# cc2652p_ch340k.net
KiCad netlist of a schematic drawn in EAGLE
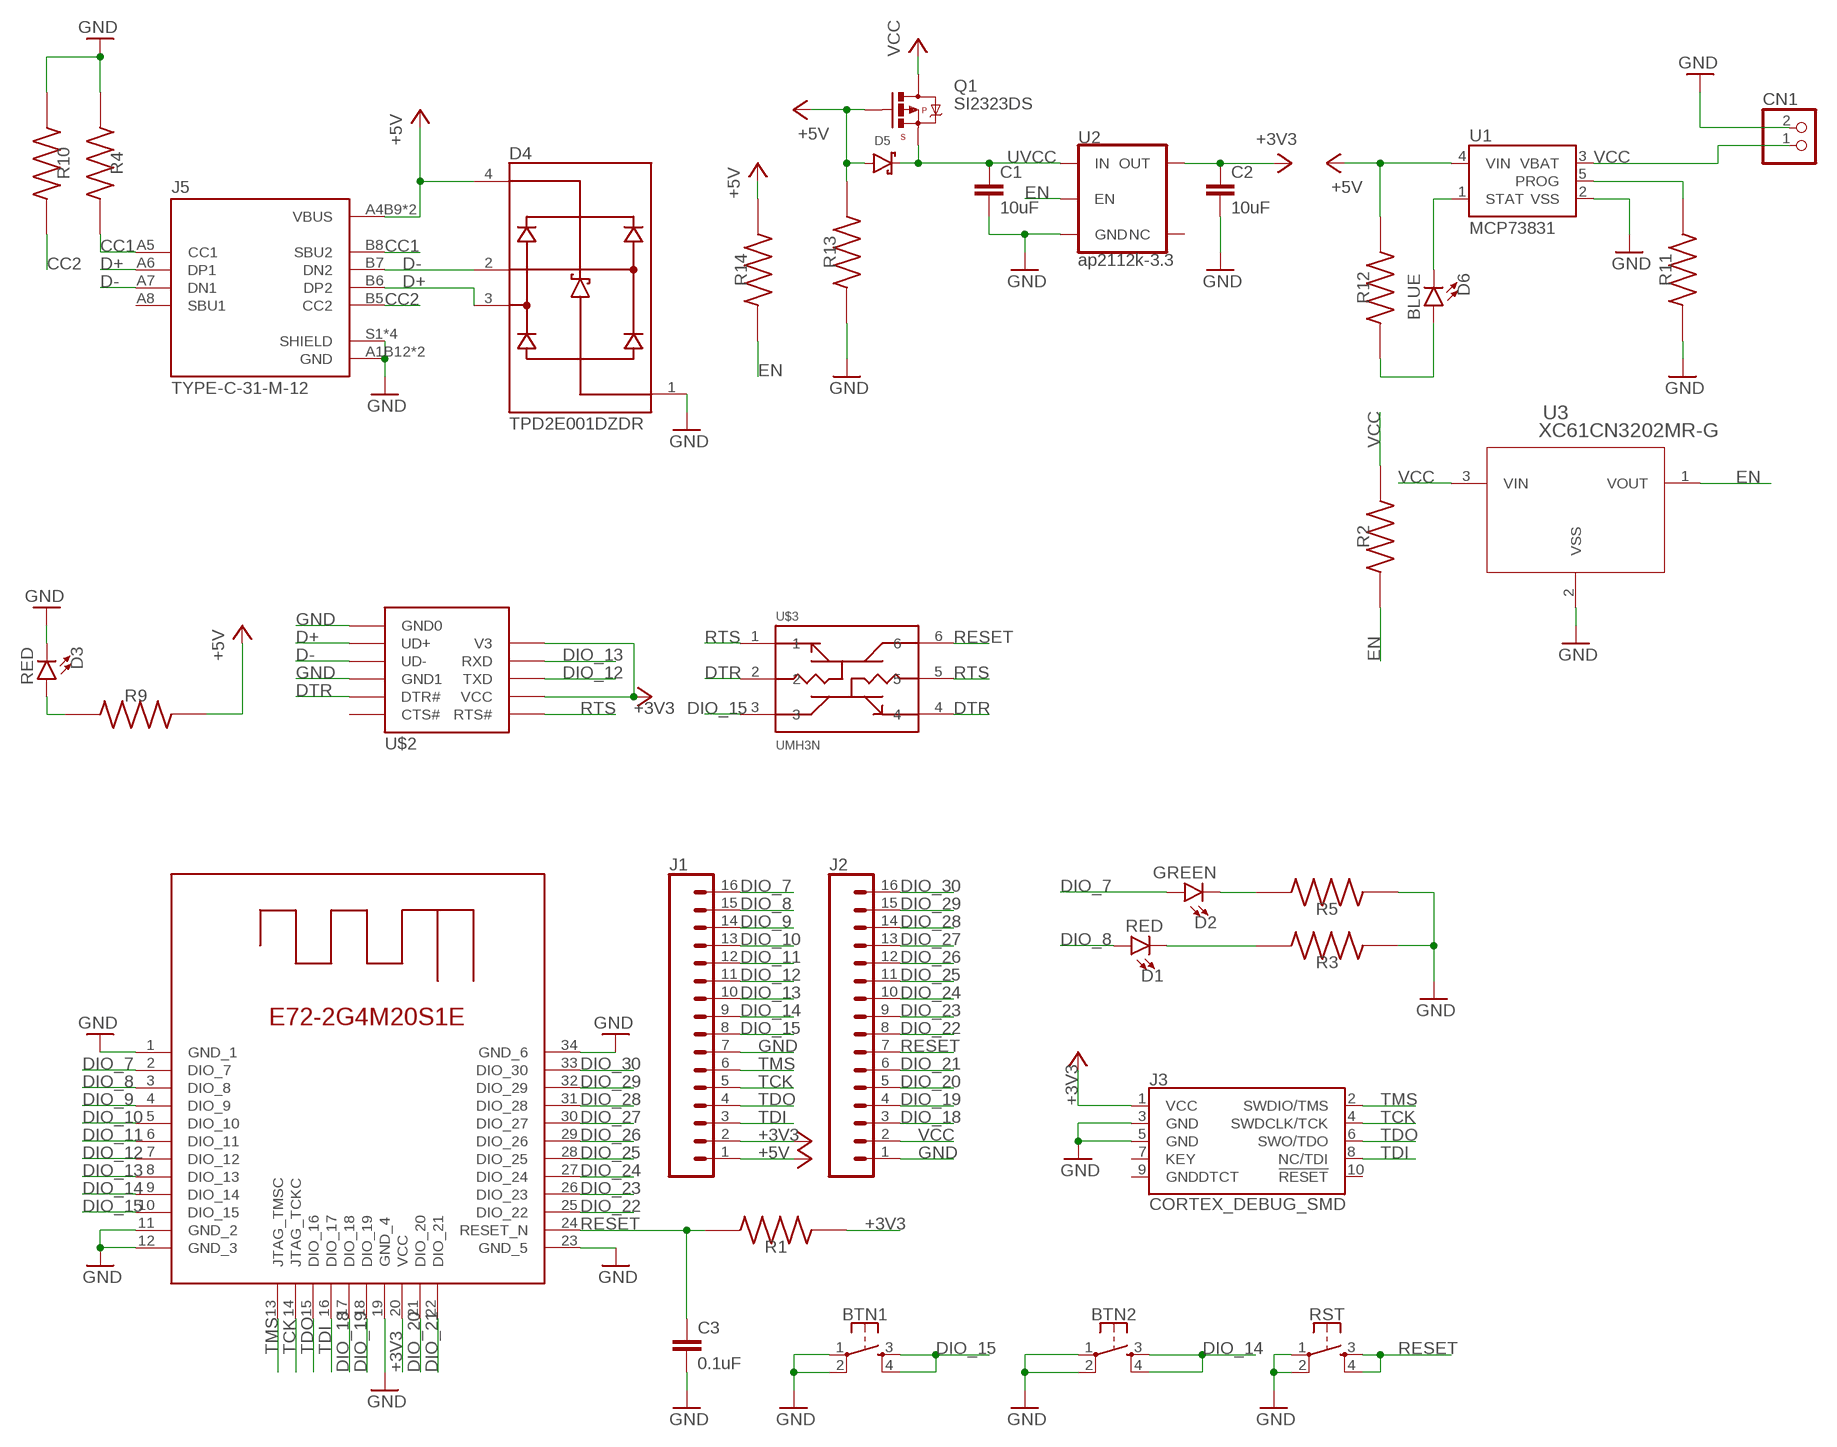
[diagram p0: schematic, sheet 1]

(export (version "E")
  (design (tool "Eeschema 10.0.6"))
  (components
    (comp (ref "BTN1")
      (value "MOMENTARY-SWITCH-SPST-2-SMD-4.6X2.8MM")
      (footprint "eagle-import:TACTILE_SWITCH_SMD_4.6X2.8MM")
      (libsource (lib "eagle-import") (part "MOMENTARY-SWITCH-SPST-2-SMD-4.6X2.8MM"))
    )
    (comp (ref "BTN2")
      (value "MOMENTARY-SWITCH-SPST-2-SMD-4.6X2.8MM")
      (footprint "eagle-import:TACTILE_SWITCH_SMD_4.6X2.8MM")
      (libsource (lib "eagle-import") (part "MOMENTARY-SWITCH-SPST-2-SMD-4.6X2.8MM"))
    )
    (comp (ref "C1")
      (value "10uF")
      (footprint "eagle-import:0603")
      (libsource (lib "eagle-import") (part "10UF-0603-6.3V-20%"))
    )
    (comp (ref "C2")
      (value "10uF")
      (footprint "eagle-import:0603")
      (libsource (lib "eagle-import") (part "10UF-0603-6.3V-20%"))
    )
    (comp (ref "C3")
      (value "0.1uF")
      (footprint "eagle-import:0603")
      (libsource (lib "eagle-import") (part "0.1UF-0603-25V-(+80/-20%)"))
    )
    (comp (ref "CN1")
      (value "JST_2PIN-SMT-RA")
      (footprint "eagle-import:JST-PH-2-SMT-RA")
      (libsource (lib "eagle-import") (part "JST_2PIN-SMT-RA"))
    )
    (comp (ref "D1")
      (value "RED")
      (footprint "eagle-import:LED-0603")
      (libsource (lib "eagle-import") (part "LED-RED0603"))
    )
    (comp (ref "D2")
      (value "GREEN")
      (footprint "eagle-import:LED-0603")
      (libsource (lib "eagle-import") (part "LED-GREEN0603"))
    )
    (comp (ref "D3")
      (value "RED")
      (footprint "eagle-import:LED-0603")
      (libsource (lib "eagle-import") (part "LED-RED0603"))
    )
    (comp (ref "D4")
      (value "TPD2E001DZDR")
      (footprint "eagle-import:SOT192P237X122-4N")
      (fields (field (name "MF") "Texas Instruments"))
      (libsource (lib "eagle-import") (part "TPD2E001DZDR"))
    )
    (comp (ref "D5")
      (value "DIODE-SCHOTTKY")
      (footprint "eagle-import:SOD-323")
      (libsource (lib "eagle-import") (part "DIODE-SCHOTTKY"))
    )
    (comp (ref "D6")
      (value "BLUE")
      (footprint "eagle-import:LED-0603")
      (libsource (lib "eagle-import") (part "LED-BLUE0603"))
    )
    (comp (ref "J1")
      (value "CONN_161X16_NO_SILK")
      (footprint "eagle-import:1X16_NO_SILK")
      (libsource (lib "eagle-import") (part "CONN_161X16_NO_SILK"))
    )
    (comp (ref "J2")
      (value "CONN_161X16_NO_SILK")
      (footprint "eagle-import:1X16_NO_SILK")
      (libsource (lib "eagle-import") (part "CONN_161X16_NO_SILK"))
    )
    (comp (ref "J3")
      (value "CORTEX_DEBUG_SMD")
      (footprint "eagle-import:SAMTECH_FTSH-105-01")
      (libsource (lib "eagle-import") (part "CORTEX_DEBUG_SMD"))
    )
    (comp (ref "J5")
      (value "TYPE-C-31-M-12")
      (footprint "eagle-import:HRO_TYPE-C-31-M-12")
      (fields (field (name "MF") "HRO Electronics Co., Ltd."))
      (libsource (lib "eagle-import") (part "TYPE-C-31-M-12"))
    )
    (comp (ref "Q1")
      (value "SI2323DS")
      (footprint "eagle-import:SOT23")
      (libsource (lib "eagle-import") (part "MOSFET-PCHANNEL"))
    )
    (comp (ref "R1")
      (value "100k")
      (footprint "eagle-import:RESC1005X40N")
      (fields (field (name "MF") "Yageo") (field (name "MP") "RC0402FR-073M6L"))
      (libsource (lib "eagle-import") (part "RC0402FR-073M6L"))
    )
    (comp (ref "R2")
      (value "10k")
      (footprint "eagle-import:RESC1005X40N")
      (fields (field (name "MF") "Yageo") (field (name "MP") "RC0402FR-073M6L"))
      (libsource (lib "eagle-import") (part "RC0402FR-073M6L"))
    )
    (comp (ref "R3")
      (value "2.2k")
      (footprint "eagle-import:RESC1005X40N")
      (fields (field (name "MF") "Yageo") (field (name "MP") "RC0402FR-073M6L"))
      (libsource (lib "eagle-import") (part "RC0402FR-073M6L"))
    )
    (comp (ref "R4")
      (value "5.1k")
      (footprint "eagle-import:RESC1005X40N")
      (fields (field (name "MF") "Yageo") (field (name "MP") "RC0402FR-073M6L"))
      (libsource (lib "eagle-import") (part "RC0402FR-073M6L"))
    )
    (comp (ref "R5")
      (value "2.2k")
      (footprint "eagle-import:RESC1005X40N")
      (fields (field (name "MF") "Yageo") (field (name "MP") "RC0402FR-073M6L"))
      (libsource (lib "eagle-import") (part "RC0402FR-073M6L"))
    )
    (comp (ref "R9")
      (value "2.2k")
      (footprint "eagle-import:RESC1005X40N")
      (fields (field (name "MF") "Yageo") (field (name "MP") "RC0402FR-073M6L"))
      (libsource (lib "eagle-import") (part "RC0402FR-073M6L"))
    )
    (comp (ref "R10")
      (value "5.1k")
      (footprint "eagle-import:RESC1005X40N")
      (fields (field (name "MF") "Yageo") (field (name "MP") "RC0402FR-073M6L"))
      (libsource (lib "eagle-import") (part "RC0402FR-073M6L"))
    )
    (comp (ref "R11")
      (value "2k")
      (footprint "eagle-import:RESC1005X40N")
      (fields (field (name "MF") "Yageo") (field (name "MP") "RC0402FR-073M6L"))
      (libsource (lib "eagle-import") (part "RC0402FR-073M6L"))
    )
    (comp (ref "R12")
      (value "2.2k")
      (footprint "eagle-import:RESC1005X40N")
      (fields (field (name "MF") "Yageo") (field (name "MP") "RC0402FR-073M6L"))
      (libsource (lib "eagle-import") (part "RC0402FR-073M6L"))
    )
    (comp (ref "R13")
      (value "10k")
      (footprint "eagle-import:RESC1005X40N")
      (fields (field (name "MF") "Yageo") (field (name "MP") "RC0402FR-073M6L"))
      (libsource (lib "eagle-import") (part "RC0402FR-073M6L"))
    )
    (comp (ref "R14")
      (value "10k")
      (footprint "eagle-import:RESC1005X40N")
      (fields (field (name "MF") "Yageo") (field (name "MP") "RC0402FR-073M6L"))
      (libsource (lib "eagle-import") (part "RC0402FR-073M6L"))
    )
    (comp (ref "RST")
      (value "MOMENTARY-SWITCH-SPST-2-SMD-4.6X2.8MM")
      (footprint "eagle-import:TACTILE_SWITCH_SMD_4.6X2.8MM")
      (libsource (lib "eagle-import") (part "MOMENTARY-SWITCH-SPST-2-SMD-4.6X2.8MM"))
    )
    (comp (ref "U$1")
      (value "E72-2G4M20S1E")
      (footprint "eagle-import:E72-2G4M20S1E")
      (libsource (lib "eagle-import") (part "E72-2G4M20S1E"))
    )
    (comp (ref "U$2")
      (value "CH340K")
      (footprint "eagle-import:ESSOP10")
      (libsource (lib "eagle-import") (part "CH340K"))
    )
    (comp (ref "U$3")
      (value "UMH3N")
      (footprint "eagle-import:SOP65P210X100-6N")
      (fields (field (name "MF") "Rohm"))
      (libsource (lib "eagle-import") (part "UMH3N"))
    )
    (comp (ref "U1")
      (value "MCP73831")
      (footprint "eagle-import:SOT23-5")
      (libsource (lib "eagle-import") (part "MCP73831"))
    )
    (comp (ref "U2")
      (value "ap2112k-3.3")
      (footprint "eagle-import:SOT23-5")
      (libsource (lib "eagle-import") (part "V_REG_AP2112K-3.3V"))
    )
    (comp (ref "U3")
      (value "XC61CN3202MR-G")
      (footprint "eagle-import:XC61C_SOT-23_TOR")
      (libsource (lib "eagle-import") (part "XC61CN3202MR-G"))
    )
  )
  (nets
    (net (code "1") (name "+3V3") (class "Default")
      (node (ref "C2") (pin "1") (pinfunction "1_1") (pintype "passive"))
      (node (ref "J1") (pin "2") (pinfunction "2_2") (pintype "passive"))
      (node (ref "J3") (pin "1") (pinfunction "VCC_1") (pintype "bidirectional"))
      (node (ref "R1") (pin "1") (pinfunction "1_1") (pintype "passive"))
      (node (ref "U$1") (pin "20") (pinfunction "VCC_20") (pintype "bidirectional"))
      (node (ref "U$2") (pin "P$6") (pinfunction "VCC_P$6") (pintype "bidirectional"))
      (node (ref "U$2") (pin "P$9") (pinfunction "V3_P$9") (pintype "bidirectional"))
      (node (ref "U2") (pin "5") (pinfunction "OUT_5") (pintype "passive"))
    )
    (net (code "2") (name "+5V") (class "Default")
      (node (ref "D4") (pin "4") (pinfunction "VCC_4") (pintype "power_in"))
      (node (ref "D5") (pin "A") (pinfunction "A_A") (pintype "passive"))
      (node (ref "J1") (pin "1") (pinfunction "1_1") (pintype "passive"))
      (node (ref "J5") (pin "A4B9") (pinfunction "VBUS_A4B9") (pintype "power_in"))
      (node (ref "J5") (pin "B4A9") (pinfunction "VBUS_B4A9") (pintype "power_in"))
      (node (ref "Q1") (pin "1") (pinfunction "G_1") (pintype "passive"))
      (node (ref "R12") (pin "2") (pinfunction "2_2") (pintype "passive"))
      (node (ref "R13") (pin "2") (pinfunction "2_2") (pintype "passive"))
      (node (ref "R14") (pin "2") (pinfunction "2_2") (pintype "passive"))
      (node (ref "R9") (pin "1") (pinfunction "1_1") (pintype "passive"))
      (node (ref "U1") (pin "4") (pinfunction "VIN_4") (pintype "power_in"))
    )
    (net (code "3") (name "/CC1") (class "Default")
      (node (ref "J5") (pin "A5") (pinfunction "CC1_A5") (pintype "bidirectional"))
      (node (ref "J5") (pin "B8") (pinfunction "SBU2_B8") (pintype "bidirectional"))
      (node (ref "R4") (pin "2") (pinfunction "2_2") (pintype "passive"))
    )
    (net (code "4") (name "/CC2") (class "Default")
      (node (ref "J5") (pin "B5") (pinfunction "CC2_B5") (pintype "bidirectional"))
      (node (ref "R10") (pin "2") (pinfunction "2_2") (pintype "passive"))
    )
    (net (code "5") (name "/D+") (class "Default")
      (node (ref "D4") (pin "3") (pinfunction "IO2_3") (pintype "bidirectional"))
      (node (ref "J5") (pin "A6") (pinfunction "DP1_A6") (pintype "bidirectional"))
      (node (ref "J5") (pin "B6") (pinfunction "DP2_B6") (pintype "bidirectional"))
      (node (ref "U$2") (pin "P$0") (pinfunction "UD+_P$0") (pintype "bidirectional"))
    )
    (net (code "6") (name "/D-") (class "Default")
      (node (ref "D4") (pin "2") (pinfunction "IO1_2") (pintype "bidirectional"))
      (node (ref "J5") (pin "A7") (pinfunction "DN1_A7") (pintype "bidirectional"))
      (node (ref "J5") (pin "B7") (pinfunction "DN2_B7") (pintype "bidirectional"))
      (node (ref "U$2") (pin "P$1") (pinfunction "UD-_P$1") (pintype "bidirectional"))
    )
    (net (code "7") (name "/DIO_7") (class "Default")
      (node (ref "D2") (pin "A") (pinfunction "A_A") (pintype "passive"))
      (node (ref "J1") (pin "16") (pinfunction "16_16") (pintype "passive"))
      (node (ref "U$1") (pin "2") (pinfunction "DIO_7_2") (pintype "bidirectional"))
    )
    (net (code "8") (name "/DIO_8") (class "Default")
      (node (ref "D1") (pin "A") (pinfunction "A_A") (pintype "passive"))
      (node (ref "J1") (pin "15") (pinfunction "15_15") (pintype "passive"))
      (node (ref "U$1") (pin "3") (pinfunction "DIO_8_3") (pintype "bidirectional"))
    )
    (net (code "9") (name "/DIO_9") (class "Default")
      (node (ref "J1") (pin "14") (pinfunction "14_14") (pintype "passive"))
      (node (ref "U$1") (pin "4") (pinfunction "DIO_9_4") (pintype "bidirectional"))
    )
    (net (code "10") (name "/DIO_10") (class "Default")
      (node (ref "J1") (pin "13") (pinfunction "13_13") (pintype "passive"))
      (node (ref "U$1") (pin "5") (pinfunction "DIO_10_5") (pintype "bidirectional"))
    )
    (net (code "11") (name "/DIO_11") (class "Default")
      (node (ref "J1") (pin "12") (pinfunction "12_12") (pintype "passive"))
      (node (ref "U$1") (pin "6") (pinfunction "DIO_11_6") (pintype "bidirectional"))
    )
    (net (code "12") (name "/DIO_12") (class "Default")
      (node (ref "J1") (pin "11") (pinfunction "11_11") (pintype "passive"))
      (node (ref "U$1") (pin "7") (pinfunction "DIO_12_7") (pintype "bidirectional"))
      (node (ref "U$2") (pin "P$7") (pinfunction "TXD_P$7") (pintype "bidirectional"))
    )
    (net (code "13") (name "/DIO_13") (class "Default")
      (node (ref "J1") (pin "10") (pinfunction "10_10") (pintype "passive"))
      (node (ref "U$1") (pin "8") (pinfunction "DIO_13_8") (pintype "bidirectional"))
      (node (ref "U$2") (pin "P$8") (pinfunction "RXD_P$8") (pintype "bidirectional"))
    )
    (net (code "14") (name "/DIO_14") (class "Default")
      (node (ref "BTN2") (pin "3") (pinfunction "3_3") (pintype "passive"))
      (node (ref "BTN2") (pin "4") (pinfunction "4_4") (pintype "passive"))
      (node (ref "J1") (pin "9") (pinfunction "9_9") (pintype "passive"))
      (node (ref "U$1") (pin "9") (pinfunction "DIO_14_9") (pintype "bidirectional"))
    )
    (net (code "15") (name "/DIO_15") (class "Default")
      (node (ref "BTN1") (pin "3") (pinfunction "3_3") (pintype "passive"))
      (node (ref "BTN1") (pin "4") (pinfunction "4_4") (pintype "passive"))
      (node (ref "J1") (pin "8") (pinfunction "8_8") (pintype "passive"))
      (node (ref "U$1") (pin "10") (pinfunction "DIO_15_10") (pintype "bidirectional"))
      (node (ref "U$3") (pin "3") (pinfunction "3_3") (pintype "bidirectional"))
    )
    (net (code "16") (name "/DIO_18") (class "Default")
      (node (ref "J2") (pin "3") (pinfunction "3_3") (pintype "passive"))
      (node (ref "U$1") (pin "17") (pinfunction "DIO_18_17") (pintype "bidirectional"))
    )
    (net (code "17") (name "/DIO_19") (class "Default")
      (node (ref "J2") (pin "4") (pinfunction "4_4") (pintype "passive"))
      (node (ref "U$1") (pin "18") (pinfunction "DIO_19_18") (pintype "bidirectional"))
    )
    (net (code "18") (name "/DIO_20") (class "Default")
      (node (ref "J2") (pin "5") (pinfunction "5_5") (pintype "passive"))
      (node (ref "U$1") (pin "21") (pinfunction "DIO_20_21") (pintype "bidirectional"))
    )
    (net (code "19") (name "/DIO_21") (class "Default")
      (node (ref "J2") (pin "6") (pinfunction "6_6") (pintype "passive"))
      (node (ref "U$1") (pin "22") (pinfunction "DIO_21_22") (pintype "bidirectional"))
    )
    (net (code "20") (name "/DIO_22") (class "Default")
      (node (ref "J2") (pin "8") (pinfunction "8_8") (pintype "passive"))
      (node (ref "U$1") (pin "25") (pinfunction "DIO_22_25") (pintype "bidirectional"))
    )
    (net (code "21") (name "/DIO_23") (class "Default")
      (node (ref "J2") (pin "9") (pinfunction "9_9") (pintype "passive"))
      (node (ref "U$1") (pin "26") (pinfunction "DIO_23_26") (pintype "bidirectional"))
    )
    (net (code "22") (name "/DIO_24") (class "Default")
      (node (ref "J2") (pin "10") (pinfunction "10_10") (pintype "passive"))
      (node (ref "U$1") (pin "27") (pinfunction "DIO_24_27") (pintype "bidirectional"))
    )
    (net (code "23") (name "/DIO_25") (class "Default")
      (node (ref "J2") (pin "11") (pinfunction "11_11") (pintype "passive"))
      (node (ref "U$1") (pin "28") (pinfunction "DIO_25_28") (pintype "bidirectional"))
    )
    (net (code "24") (name "/DIO_26") (class "Default")
      (node (ref "J2") (pin "12") (pinfunction "12_12") (pintype "passive"))
      (node (ref "U$1") (pin "29") (pinfunction "DIO_26_29") (pintype "bidirectional"))
    )
    (net (code "25") (name "/DIO_27") (class "Default")
      (node (ref "J2") (pin "13") (pinfunction "13_13") (pintype "passive"))
      (node (ref "U$1") (pin "30") (pinfunction "DIO_27_30") (pintype "bidirectional"))
    )
    (net (code "26") (name "/DIO_28") (class "Default")
      (node (ref "J2") (pin "14") (pinfunction "14_14") (pintype "passive"))
      (node (ref "U$1") (pin "31") (pinfunction "DIO_28_31") (pintype "bidirectional"))
    )
    (net (code "27") (name "/DIO_29") (class "Default")
      (node (ref "J2") (pin "15") (pinfunction "15_15") (pintype "passive"))
      (node (ref "U$1") (pin "32") (pinfunction "DIO_29_32") (pintype "bidirectional"))
    )
    (net (code "28") (name "/DIO_30") (class "Default")
      (node (ref "J2") (pin "16") (pinfunction "16_16") (pintype "passive"))
      (node (ref "U$1") (pin "33") (pinfunction "DIO_30_33") (pintype "bidirectional"))
    )
    (net (code "29") (name "/DTR") (class "Default")
      (node (ref "U$2") (pin "P$3") (pinfunction "DTR#_P$3") (pintype "bidirectional"))
      (node (ref "U$3") (pin "2") (pinfunction "2_2") (pintype "bidirectional"))
      (node (ref "U$3") (pin "4") (pinfunction "4_4") (pintype "bidirectional"))
    )
    (net (code "30") (name "/EN") (class "Default")
      (node (ref "R14") (pin "1") (pinfunction "1_1") (pintype "passive"))
      (node (ref "R2") (pin "1") (pinfunction "1_1") (pintype "passive"))
      (node (ref "U2") (pin "3") (pinfunction "EN_3") (pintype "input"))
      (node (ref "U3") (pin "1") (pinfunction "VOUT_1") (pintype "output"))
    )
    (net (code "31") (name "/RESET") (class "Default")
      (node (ref "C3") (pin "1") (pinfunction "1_1") (pintype "passive"))
      (node (ref "J2") (pin "7") (pinfunction "7_7") (pintype "passive"))
      (node (ref "R1") (pin "2") (pinfunction "2_2") (pintype "passive"))
      (node (ref "RST") (pin "3") (pinfunction "3_3") (pintype "passive"))
      (node (ref "RST") (pin "4") (pinfunction "4_4") (pintype "passive"))
      (node (ref "U$1") (pin "24") (pinfunction "RESET_N_24") (pintype "bidirectional"))
      (node (ref "U$3") (pin "6") (pinfunction "6_6") (pintype "bidirectional"))
    )
    (net (code "32") (name "/RTS") (class "Default")
      (node (ref "U$2") (pin "P$5") (pinfunction "RTS#_P$5") (pintype "bidirectional"))
      (node (ref "U$3") (pin "1") (pinfunction "1_1") (pintype "bidirectional"))
      (node (ref "U$3") (pin "5") (pinfunction "5_5") (pintype "bidirectional"))
    )
    (net (code "33") (name "/TCK") (class "Default")
      (node (ref "J1") (pin "5") (pinfunction "5_5") (pintype "passive"))
      (node (ref "J3") (pin "4") (pinfunction "SWDCLK/TCK_4") (pintype "bidirectional"))
      (node (ref "U$1") (pin "14") (pinfunction "JTAG_TCKC_14") (pintype "bidirectional"))
    )
    (net (code "34") (name "/TDI") (class "Default")
      (node (ref "J1") (pin "3") (pinfunction "3_3") (pintype "passive"))
      (node (ref "J3") (pin "8") (pinfunction "NC/TDI_8") (pintype "bidirectional"))
      (node (ref "U$1") (pin "16") (pinfunction "DIO_17_16") (pintype "bidirectional"))
    )
    (net (code "35") (name "/TDO") (class "Default")
      (node (ref "J1") (pin "4") (pinfunction "4_4") (pintype "passive"))
      (node (ref "J3") (pin "6") (pinfunction "SWO/TDO_6") (pintype "bidirectional"))
      (node (ref "U$1") (pin "15") (pinfunction "DIO_16_15") (pintype "bidirectional"))
    )
    (net (code "36") (name "/TMS") (class "Default")
      (node (ref "J1") (pin "6") (pinfunction "6_6") (pintype "passive"))
      (node (ref "J3") (pin "2") (pinfunction "SWDIO/TMS_2") (pintype "bidirectional"))
      (node (ref "U$1") (pin "13") (pinfunction "JTAG_TMSC_13") (pintype "bidirectional"))
    )
    (net (code "37") (name "/UVCC") (class "Default")
      (node (ref "C1") (pin "1") (pinfunction "1_1") (pintype "passive"))
      (node (ref "D5") (pin "C") (pinfunction "C_C") (pintype "passive"))
      (node (ref "Q1") (pin "2") (pinfunction "S_2") (pintype "passive"))
      (node (ref "U2") (pin "1") (pinfunction "IN_1") (pintype "input"))
    )
    (net (code "38") (name "GND") (class "Default")
      (node (ref "BTN1") (pin "1") (pinfunction "1_1") (pintype "passive"))
      (node (ref "BTN1") (pin "2") (pinfunction "2_2") (pintype "passive"))
      (node (ref "BTN2") (pin "1") (pinfunction "1_1") (pintype "passive"))
      (node (ref "BTN2") (pin "2") (pinfunction "2_2") (pintype "passive"))
      (node (ref "C1") (pin "2") (pinfunction "2_2") (pintype "passive"))
      (node (ref "C2") (pin "2") (pinfunction "2_2") (pintype "passive"))
      (node (ref "C3") (pin "2") (pinfunction "2_2") (pintype "passive"))
      (node (ref "CN1") (pin "2") (pinfunction "1_2") (pintype "passive"))
      (node (ref "D3") (pin "C") (pinfunction "C_C") (pintype "passive"))
      (node (ref "D4") (pin "1") (pinfunction "GND_1") (pintype "power_in"))
      (node (ref "J1") (pin "7") (pinfunction "7_7") (pintype "passive"))
      (node (ref "J2") (pin "1") (pinfunction "1_1") (pintype "passive"))
      (node (ref "J3") (pin "3") (pinfunction "GND_3") (pintype "bidirectional"))
      (node (ref "J3") (pin "5") (pinfunction "GND_5") (pintype "bidirectional"))
      (node (ref "J5") (pin "A1B12") (pinfunction "GND_A1B12") (pintype "power_in"))
      (node (ref "J5") (pin "B1A12") (pinfunction "GND_B1A12") (pintype "power_in"))
      (node (ref "J5") (pin "S1") (pinfunction "SHIELD_S1") (pintype "passive"))
      (node (ref "J5") (pin "S2") (pinfunction "SHIELD_S2") (pintype "passive"))
      (node (ref "J5") (pin "S3") (pinfunction "SHIELD_S3") (pintype "passive"))
      (node (ref "J5") (pin "S4") (pinfunction "SHIELD_S4") (pintype "passive"))
      (node (ref "R10") (pin "1") (pinfunction "1_1") (pintype "passive"))
      (node (ref "R11") (pin "1") (pinfunction "1_1") (pintype "passive"))
      (node (ref "R13") (pin "1") (pinfunction "1_1") (pintype "passive"))
      (node (ref "R3") (pin "1") (pinfunction "1_1") (pintype "passive"))
      (node (ref "R4") (pin "1") (pinfunction "1_1") (pintype "passive"))
      (node (ref "R5") (pin "1") (pinfunction "1_1") (pintype "passive"))
      (node (ref "RST") (pin "1") (pinfunction "1_1") (pintype "passive"))
      (node (ref "RST") (pin "2") (pinfunction "2_2") (pintype "passive"))
      (node (ref "U$1") (pin "1") (pinfunction "GND_1_1") (pintype "bidirectional"))
      (node (ref "U$1") (pin "11") (pinfunction "GND_2_11") (pintype "bidirectional"))
      (node (ref "U$1") (pin "12") (pinfunction "GND_3_12") (pintype "bidirectional"))
      (node (ref "U$1") (pin "19") (pinfunction "GND_4_19") (pintype "bidirectional"))
      (node (ref "U$1") (pin "23") (pinfunction "GND_5_23") (pintype "bidirectional"))
      (node (ref "U$1") (pin "34") (pinfunction "GND_6_34") (pintype "bidirectional"))
      (node (ref "U$2") (pin "P$10") (pinfunction "GND0_P$10") (pintype "bidirectional"))
      (node (ref "U$2") (pin "P$2") (pinfunction "GND1_P$2") (pintype "bidirectional"))
      (node (ref "U1") (pin "2") (pinfunction "VSS_2") (pintype "power_in"))
      (node (ref "U2") (pin "2") (pinfunction "GND_2") (pintype "input"))
      (node (ref "U3") (pin "2") (pinfunction "VSS_2") (pintype "passive"))
    )
    (net (code "39") (name "Net-(D1-PadC)") (class "Default")
      (node (ref "D1") (pin "C") (pinfunction "C_C") (pintype "passive"))
      (node (ref "R3") (pin "2") (pinfunction "2_2") (pintype "passive"))
    )
    (net (code "40") (name "Net-(D2-PadC)") (class "Default")
      (node (ref "D2") (pin "C") (pinfunction "C_C") (pintype "passive"))
      (node (ref "R5") (pin "2") (pinfunction "2_2") (pintype "passive"))
    )
    (net (code "41") (name "Net-(D3-PadA)") (class "Default")
      (node (ref "D3") (pin "A") (pinfunction "A_A") (pintype "passive"))
      (node (ref "R9") (pin "2") (pinfunction "2_2") (pintype "passive"))
    )
    (net (code "42") (name "Net-(D6-PadA)") (class "Default")
      (node (ref "D6") (pin "A") (pinfunction "A_A") (pintype "passive"))
      (node (ref "R12") (pin "1") (pinfunction "1_1") (pintype "passive"))
    )
    (net (code "43") (name "Net-(U1-PROG)") (class "Default")
      (node (ref "R11") (pin "2") (pinfunction "2_2") (pintype "passive"))
      (node (ref "U1") (pin "5") (pinfunction "PROG_5") (pintype "input"))
    )
    (net (code "44") (name "Net-(U1-STAT)") (class "Default")
      (node (ref "D6") (pin "C") (pinfunction "C_C") (pintype "passive"))
      (node (ref "U1") (pin "1") (pinfunction "STAT_1") (pintype "output"))
    )
    (net (code "45") (name "VCC") (class "Default")
      (node (ref "CN1") (pin "1") (pinfunction "2_1") (pintype "passive"))
      (node (ref "J2") (pin "2") (pinfunction "2_2") (pintype "passive"))
      (node (ref "Q1") (pin "3") (pinfunction "D_3") (pintype "passive"))
      (node (ref "R2") (pin "2") (pinfunction "2_2") (pintype "passive"))
      (node (ref "U1") (pin "3") (pinfunction "VBAT_3") (pintype "power_in"))
      (node (ref "U3") (pin "3") (pinfunction "VIN_3") (pintype "power_in"))
    )
    (net (code "46") (name "unconnected-(J3-GNDDTCT-Pad9)") (class "Default")
      (node (ref "J3") (pin "9") (pinfunction "GNDDTCT_9") (pintype "bidirectional"))
    )
    (net (code "47") (name "unconnected-(J3-KEY-Pad7)") (class "Default")
      (node (ref "J3") (pin "7") (pinfunction "KEY_7") (pintype "bidirectional"))
    )
    (net (code "48") (name "unconnected-(J3-~{RESET}-Pad10)") (class "Default")
      (node (ref "J3") (pin "10") (pinfunction "~{RESET}_10") (pintype "bidirectional"))
    )
    (net (code "49") (name "unconnected-(J5-SBU1-PadA8)") (class "Default")
      (node (ref "J5") (pin "A8") (pinfunction "SBU1_A8") (pintype "bidirectional"))
    )
    (net (code "50") (name "unconnected-(U$2-CTS#-PadP$4)") (class "Default")
      (node (ref "U$2") (pin "P$4") (pinfunction "CTS#_P$4") (pintype "bidirectional"))
    )
    (net (code "51") (name "unconnected-(U2-NC-Pad4)") (class "Default")
      (node (ref "U2") (pin "4") (pinfunction "NC_4") (pintype "no_connect"))
    )
  )
)
